# design.net
KiCad netlist of a schematic drawn in Altium Designer
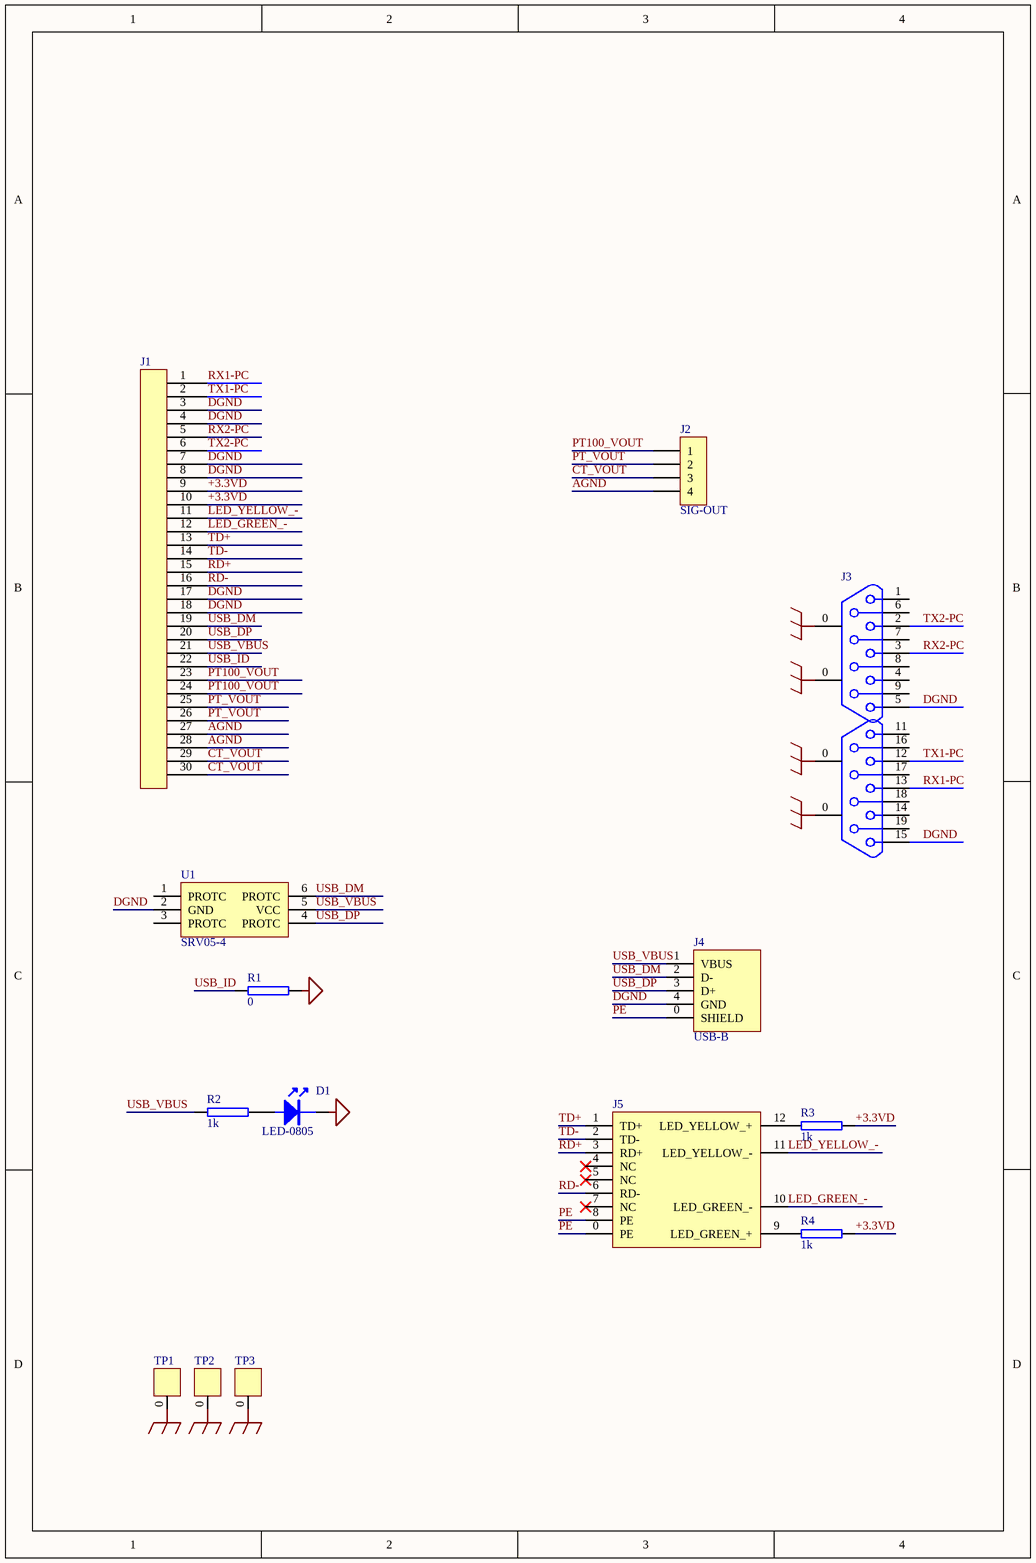
[diagram p0: 故指测试架接口板.SchDoc]

(export (version "E")
  (design (tool "Eeschema 10.0.6"))
  (components
    (comp (ref "D1") (value "LED-0805") (footprint "LED-0805") (libsource (lib "MPPT-LA") (part "LED-0805")))
    (comp (ref "J1")
      (value "~")
      (footprint "IDC-30")
      (description "CON30")
      (libsource (lib "主板") (part "CON30"))
    )
    (comp (ref "J2")
      (value "SIG-OUT")
      (footprint "KF2EDG3.81")
      (description "Connector")
      (libsource (lib "测试架_1") (part "CON4"))
    )
    (comp (ref "J3") (value "~") (footprint "DB9-2F") (libsource (lib "故指测试架接口板") (part "DB9-2F")))
    (comp (ref "J4") (value "USB-B") (footprint "USB-B") (libsource (lib "测试架接口电路板_1") (part "USB-B")))
    (comp (ref "J5")
      (value "~")
      (footprint "HR911105A")
      (description "HR911105A")
      (libsource (lib "测试架接口电路板_1") (part "HR911105A"))
    )
    (comp (ref "R1") (value "0") (footprint "0805") (libsource (lib "PCB_Project1") (part "R")))
    (comp (ref "R2") (value "1k") (footprint "0805") (libsource (lib "PCB_Project1") (part "R")))
    (comp (ref "R3") (value "1k") (footprint "0805") (libsource (lib "PCB_Project1") (part "R")))
    (comp (ref "R4") (value "1k") (footprint "0805") (libsource (lib "PCB_Project1") (part "R")))
    (comp (ref "TP1") (value "~") (footprint "PAD4.5") (libsource (lib "主板_1") (part "TESTPT")))
    (comp (ref "TP2") (value "~") (footprint "PAD4.5") (libsource (lib "主板_1") (part "TESTPT")))
    (comp (ref "TP3") (value "~") (footprint "PAD4.5") (libsource (lib "主板_1") (part "TESTPT")))
    (comp (ref "U1") (value "SRV05-4") (footprint "SOT23-6") (libsource (lib "测试架_1") (part "SRV05-4")))
  )
  (nets
    (net (code "1") (name "/+3.3VD") (class "Default")
      (node (ref "J1") (pin "10") (pintype "passive"))
      (node (ref "J1") (pin "9") (pintype "passive"))
      (node (ref "R3") (pin "2") (pinfunction "2_2") (pintype "passive"))
      (node (ref "R4") (pin "2") (pinfunction "2_2") (pintype "passive"))
    )
    (net (code "2") (name "/AGND") (class "Default")
      (node (ref "J1") (pin "27") (pinfunction "27_27") (pintype "passive"))
      (node (ref "J1") (pin "28") (pinfunction "28_28") (pintype "passive"))
      (node (ref "J2") (pin "4") (pinfunction "4_4") (pintype "passive"))
    )
    (net (code "3") (name "/CT_VOUT") (class "Default")
      (node (ref "J1") (pin "29") (pinfunction "29_29") (pintype "passive"))
      (node (ref "J1") (pin "30") (pinfunction "30_30") (pintype "passive"))
      (node (ref "J2") (pin "3") (pinfunction "3_3") (pintype "passive"))
    )
    (net (code "4") (name "/LED_GREEN_-") (class "Default")
      (node (ref "J1") (pin "12") (pintype "passive"))
      (node (ref "J5") (pin "10") (pinfunction "LED_GREEN_-_10") (pintype "passive"))
    )
    (net (code "5") (name "/LED_YELLOW_-") (class "Default")
      (node (ref "J1") (pin "11") (pintype "passive"))
      (node (ref "J5") (pin "11") (pinfunction "LED_YELLOW_-_11") (pintype "passive"))
    )
    (net (code "6") (name "/PT100_VOUT") (class "Default")
      (node (ref "J1") (pin "23") (pinfunction "23_23") (pintype "passive"))
      (node (ref "J1") (pin "24") (pinfunction "24_24") (pintype "passive"))
      (node (ref "J2") (pin "1") (pinfunction "1_1") (pintype "passive"))
    )
    (net (code "7") (name "/PT_VOUT") (class "Default")
      (node (ref "J1") (pin "25") (pinfunction "25_25") (pintype "passive"))
      (node (ref "J1") (pin "26") (pinfunction "26_26") (pintype "passive"))
      (node (ref "J2") (pin "2") (pinfunction "2_2") (pintype "passive"))
    )
    (net (code "8") (name "/RD+") (class "Default")
      (node (ref "J1") (pin "15") (pintype "passive"))
      (node (ref "J5") (pin "3") (pinfunction "RD+_3") (pintype "passive"))
    )
    (net (code "9") (name "/RD-") (class "Default")
      (node (ref "J1") (pin "16") (pintype "passive"))
      (node (ref "J5") (pin "6") (pinfunction "RD-_6") (pintype "passive"))
    )
    (net (code "10") (name "/RX1-PC") (class "Default")
      (node (ref "J1") (pin "1") (pintype "passive"))
      (node (ref "J3") (pin "13") (pinfunction "13_13") (pintype "passive"))
    )
    (net (code "11") (name "/RX2-PC") (class "Default")
      (node (ref "J1") (pin "5") (pintype "passive"))
      (node (ref "J3") (pin "3") (pinfunction "3_3") (pintype "passive"))
    )
    (net (code "12") (name "/TD+") (class "Default")
      (node (ref "J1") (pin "13") (pintype "passive"))
      (node (ref "J5") (pin "1") (pinfunction "TD+_1") (pintype "passive"))
    )
    (net (code "13") (name "/TD-") (class "Default")
      (node (ref "J1") (pin "14") (pintype "passive"))
      (node (ref "J5") (pin "2") (pinfunction "TD-_2") (pintype "passive"))
    )
    (net (code "14") (name "/TX1-PC") (class "Default")
      (node (ref "J1") (pin "2") (pintype "passive"))
      (node (ref "J3") (pin "12") (pinfunction "12_12") (pintype "passive"))
    )
    (net (code "15") (name "/TX2-PC") (class "Default")
      (node (ref "J1") (pin "6") (pintype "passive"))
      (node (ref "J3") (pin "2") (pinfunction "2_2") (pintype "passive"))
    )
    (net (code "16") (name "/USB_DM") (class "Default")
      (node (ref "J1") (pin "19") (pintype "passive"))
      (node (ref "J4") (pin "2") (pinfunction "D-_2") (pintype "passive"))
      (node (ref "U1") (pin "6") (pinfunction "PROTC_6") (pintype "passive"))
    )
    (net (code "17") (name "/USB_DP") (class "Default")
      (node (ref "J1") (pin "20") (pintype "passive"))
      (node (ref "J4") (pin "3") (pinfunction "D+_3") (pintype "passive"))
      (node (ref "U1") (pin "4") (pinfunction "PROTC_4") (pintype "passive"))
    )
    (net (code "18") (name "/USB_ID") (class "Default")
      (node (ref "J1") (pin "22") (pinfunction "22_22") (pintype "passive"))
      (node (ref "R1") (pin "2") (pinfunction "2_2") (pintype "passive"))
    )
    (net (code "19") (name "/USB_VBUS") (class "Default")
      (node (ref "J1") (pin "21") (pinfunction "21_21") (pintype "passive"))
      (node (ref "J4") (pin "1") (pinfunction "VBUS_1") (pintype "passive"))
      (node (ref "R2") (pin "1") (pinfunction "1_1") (pintype "passive"))
      (node (ref "U1") (pin "5") (pinfunction "VCC_5") (pintype "passive"))
    )
    (net (code "20") (name "DGND") (class "Default")
      (node (ref "D1") (pin "2") (pinfunction "K_2") (pintype "passive"))
      (node (ref "J1") (pin "17") (pintype "passive"))
      (node (ref "J1") (pin "18") (pintype "passive"))
      (node (ref "J1") (pin "3") (pintype "passive"))
      (node (ref "J1") (pin "4") (pintype "passive"))
      (node (ref "J1") (pin "7") (pintype "passive"))
      (node (ref "J1") (pin "8") (pintype "passive"))
      (node (ref "J3") (pin "15") (pinfunction "15_15") (pintype "passive"))
      (node (ref "J3") (pin "5") (pinfunction "5_5") (pintype "passive"))
      (node (ref "J4") (pin "4") (pinfunction "GND_4") (pintype "passive"))
      (node (ref "R1") (pin "1") (pinfunction "1_1") (pintype "passive"))
      (node (ref "U1") (pin "2") (pinfunction "GND_2") (pintype "passive"))
    )
    (net (code "21") (name "Net-(D1-A)") (class "Default")
      (node (ref "D1") (pin "1") (pinfunction "A_1") (pintype "passive"))
      (node (ref "R2") (pin "2") (pinfunction "2_2") (pintype "passive"))
    )
    (net (code "22") (name "Net-(J5-LED_GREEN_+)") (class "Default")
      (node (ref "J5") (pin "9") (pinfunction "LED_GREEN_+_9") (pintype "passive"))
      (node (ref "R4") (pin "1") (pinfunction "1_1") (pintype "passive"))
    )
    (net (code "23") (name "Net-(J5-LED_YELLOW_+)") (class "Default")
      (node (ref "J5") (pin "12") (pinfunction "LED_YELLOW_+_12") (pintype "passive"))
      (node (ref "R3") (pin "1") (pinfunction "1_1") (pintype "passive"))
    )
    (net (code "24") (name "PE") (class "Default")
      (node (ref "J3") (pin "0") (pinfunction "0_0") (pintype "passive"))
      (node (ref "J4") (pin "0") (pinfunction "SHIELD_0") (pintype "passive"))
      (node (ref "J5") (pin "0") (pinfunction "PE_0") (pintype "passive"))
      (node (ref "J5") (pin "8") (pinfunction "PE_8") (pintype "passive"))
      (node (ref "TP1") (pin "0") (pinfunction "0_0") (pintype "passive"))
      (node (ref "TP2") (pin "0") (pinfunction "0_0") (pintype "passive"))
      (node (ref "TP3") (pin "0") (pinfunction "0_0") (pintype "passive"))
    )
    (net (code "25") (name "unconnected-(J3-Pad1)") (class "Default")
      (node (ref "J3") (pin "1") (pinfunction "1_1") (pintype "passive"))
    )
    (net (code "26") (name "unconnected-(J3-Pad4)") (class "Default")
      (node (ref "J3") (pin "4") (pinfunction "4_4") (pintype "passive"))
    )
    (net (code "27") (name "unconnected-(J3-Pad6)") (class "Default")
      (node (ref "J3") (pin "6") (pinfunction "6_6") (pintype "passive"))
    )
    (net (code "28") (name "unconnected-(J3-Pad7)") (class "Default")
      (node (ref "J3") (pin "7") (pinfunction "7_7") (pintype "passive"))
    )
    (net (code "29") (name "unconnected-(J3-Pad8)") (class "Default")
      (node (ref "J3") (pin "8") (pinfunction "8_8") (pintype "passive"))
    )
    (net (code "30") (name "unconnected-(J3-Pad9)") (class "Default")
      (node (ref "J3") (pin "9") (pinfunction "9_9") (pintype "passive"))
    )
    (net (code "31") (name "unconnected-(J3-Pad11)") (class "Default")
      (node (ref "J3") (pin "11") (pinfunction "11_11") (pintype "passive"))
    )
    (net (code "32") (name "unconnected-(J3-Pad14)") (class "Default")
      (node (ref "J3") (pin "14") (pinfunction "14_14") (pintype "passive"))
    )
    (net (code "33") (name "unconnected-(J3-Pad16)") (class "Default")
      (node (ref "J3") (pin "16") (pinfunction "16_16") (pintype "passive"))
    )
    (net (code "34") (name "unconnected-(J3-Pad17)") (class "Default")
      (node (ref "J3") (pin "17") (pinfunction "17_17") (pintype "passive"))
    )
    (net (code "35") (name "unconnected-(J3-Pad18)") (class "Default")
      (node (ref "J3") (pin "18") (pinfunction "18_18") (pintype "passive"))
    )
    (net (code "36") (name "unconnected-(J3-Pad19)") (class "Default")
      (node (ref "J3") (pin "19") (pinfunction "19_19") (pintype "passive"))
    )
    (net (code "37") (name "unconnected-(J5-NC-Pad4)") (class "Default")
      (node (ref "J5") (pin "4") (pinfunction "NC_4") (pintype "passive+no_connect"))
    )
    (net (code "38") (name "unconnected-(J5-NC-Pad5)") (class "Default")
      (node (ref "J5") (pin "5") (pinfunction "NC_5") (pintype "passive+no_connect"))
    )
    (net (code "39") (name "unconnected-(J5-NC-Pad7)") (class "Default")
      (node (ref "J5") (pin "7") (pinfunction "NC_7") (pintype "passive+no_connect"))
    )
    (net (code "40") (name "unconnected-(U1-PROTC-Pad1)") (class "Default")
      (node (ref "U1") (pin "1") (pinfunction "PROTC_1") (pintype "passive"))
    )
    (net (code "41") (name "unconnected-(U1-PROTC-Pad3)") (class "Default")
      (node (ref "U1") (pin "3") (pinfunction "PROTC_3") (pintype "passive"))
    )
  )
)
